# optical.net
KiCad netlist of a schematic drawn in Altium Designer
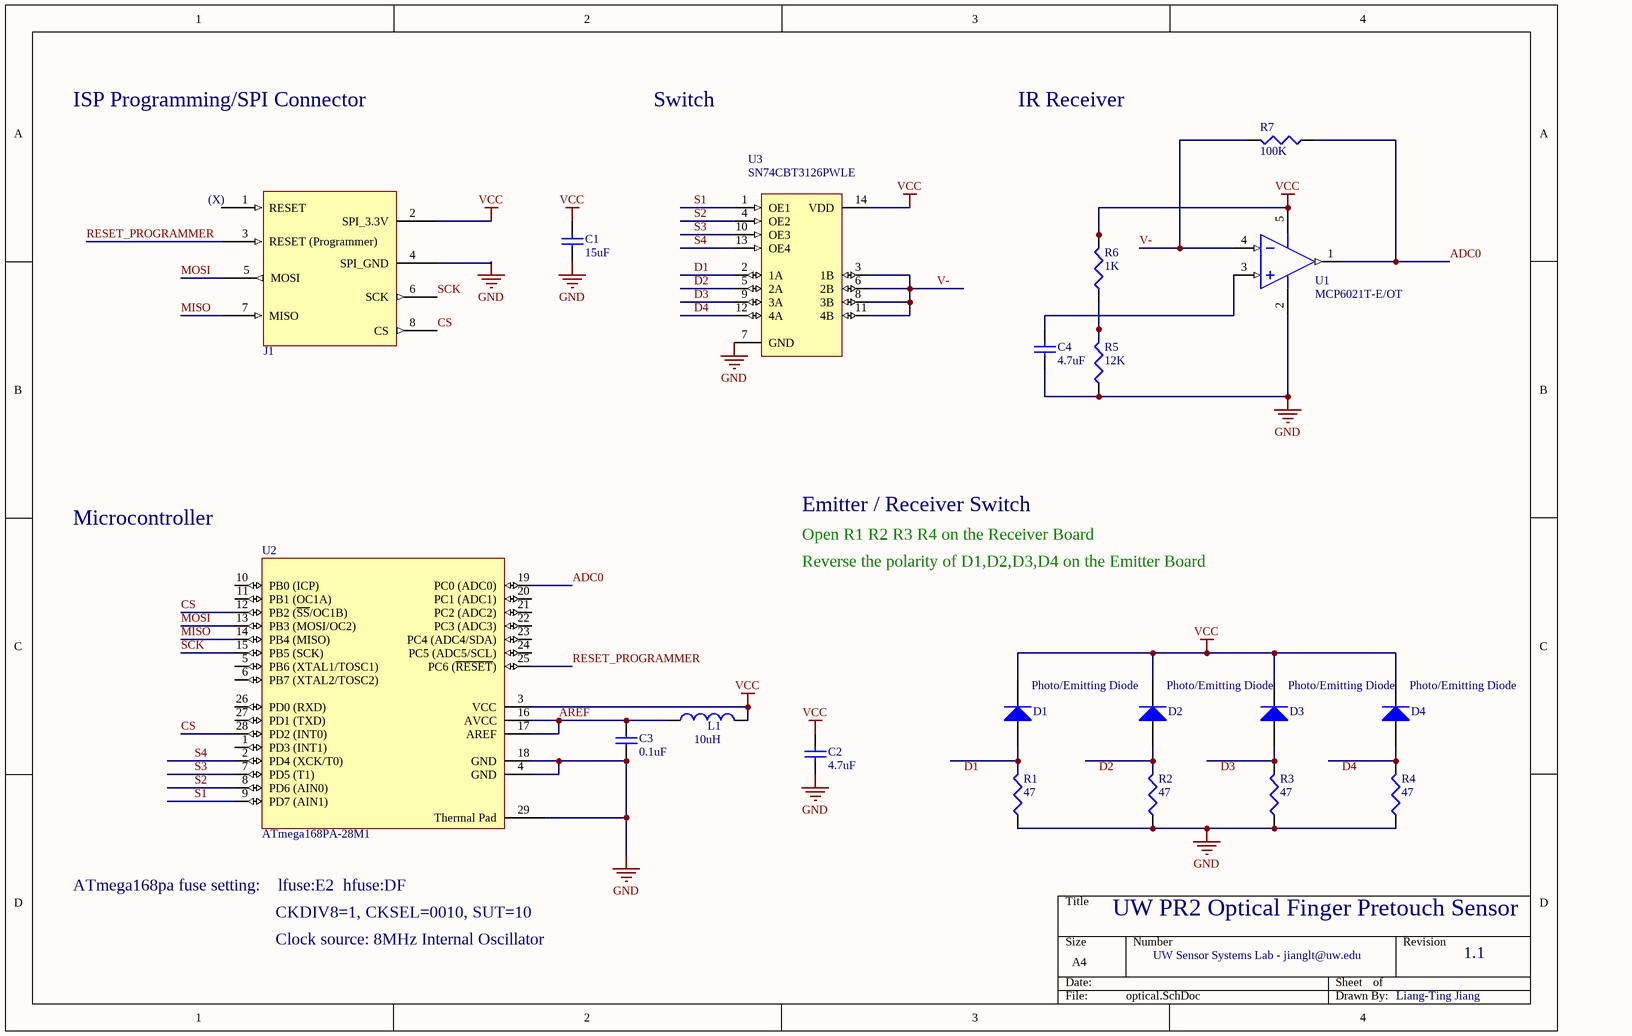
[diagram p0: optical.SchDoc]

(export (version "E")
  (design (tool "Eeschema 10.0.6"))
  (components
    (comp (ref "C1")
      (value "15uF")
      (footprint "CAPC1608N")
      (description "0603 SMD Capacitor")
      (fields (field (name "PUBLISHER") "Altium Limited"))
      (libsource (lib "Miscellaneous Devices") (part "Cap Semi"))
    )
    (comp (ref "C2")
      (value "4.7uF")
      (footprint "CAPC1608N")
      (description "0603 SMD Capacitor")
      (fields (field (name "PUBLISHER") "Altium Limited"))
      (libsource (lib "Miscellaneous Devices") (part "Cap Semi"))
    )
    (comp (ref "C3")
      (value "0.1uF")
      (footprint "CAPC1608N")
      (description "0603 SMD Capacitor")
      (fields (field (name "PUBLISHER") "Altium Limited"))
      (libsource (lib "Miscellaneous Devices") (part "Cap Semi"))
    )
    (comp (ref "C4")
      (value "4.7uF")
      (footprint "CAPC1608N")
      (description "0603 SMD Capacitor")
      (fields (field (name "PUBLISHER") "Altium Limited"))
      (libsource (lib "Miscellaneous Devices") (part "Cap Semi"))
    )
    (comp (ref "D1")
      (value "Photo/Emitting Diode")
      (footprint "Vishay VEMD/VSMB footprint")
      (description "Emitting/Photo Diode 940nm Gullwing")
      (fields (field (name "PUBLISHER") "Altium Limited"))
      (libsource (lib "Miscellaneous Devices") (part "Diode"))
    )
    (comp (ref "D2")
      (value "Photo/Emitting Diode")
      (footprint "Vishay VEMD/VSMB footprint")
      (description "Emitting/Photo Diode 940nm Gullwing")
      (fields (field (name "PUBLISHER") "Altium Limited"))
      (libsource (lib "Miscellaneous Devices") (part "Diode"))
    )
    (comp (ref "D3")
      (value "Photo/Emitting Diode")
      (footprint "Vishay VEMD/VSMB footprint")
      (description "Emitting/Photo Diode 940nm Gullwing")
      (fields (field (name "PUBLISHER") "Altium Limited"))
      (libsource (lib "Miscellaneous Devices") (part "Diode"))
    )
    (comp (ref "D4")
      (value "Photo/Emitting Diode")
      (footprint "Vishay VEMD/VSMB footprint")
      (description "Emitting/Photo Diode 940nm Gullwing")
      (fields (field (name "PUBLISHER") "Altium Limited"))
      (libsource (lib "Miscellaneous Devices") (part "Diode"))
    )
    (comp (ref "J1")
      (value "FFC 8-PIN Connector (1mm)")
      (footprint "Hirose FFC connector 8-Pin")
      (description "FFC 8-PIN Connector (1mm) (SMT)")
      (libsource (lib "UW_PR2_FINERTIP_COMPONENTS") (part "FFC Connector-8Pin-SMT-1mm"))
    )
    (comp (ref "L1")
      (value "10uH")
      (footprint "INDC1608N")
      (description "0603 SMD Inductor")
      (fields (field (name "PUBLISHER") "Altium Limited"))
      (libsource (lib "Miscellaneous Devices") (part "Inductor"))
    )
    (comp (ref "R1")
      (value "47")
      (footprint "RESC1608N")
      (description "0603 SMD Resistor")
      (fields (field (name "PUBLISHER") "Altium Limited"))
      (libsource (lib "Miscellaneous Devices") (part "Res3"))
    )
    (comp (ref "R2")
      (value "47")
      (footprint "RESC1608N")
      (description "0603 SMD Resistor")
      (fields (field (name "PUBLISHER") "Altium Limited"))
      (libsource (lib "Miscellaneous Devices") (part "Res3"))
    )
    (comp (ref "R3")
      (value "47")
      (footprint "RESC1608N")
      (description "0603 SMD Resistor")
      (fields (field (name "PUBLISHER") "Altium Limited"))
      (libsource (lib "Miscellaneous Devices") (part "Res3"))
    )
    (comp (ref "R4")
      (value "47")
      (footprint "RESC1608N")
      (description "0603 SMD Resistor")
      (fields (field (name "PUBLISHER") "Altium Limited"))
      (libsource (lib "Miscellaneous Devices") (part "Res3"))
    )
    (comp (ref "R5")
      (value "12K")
      (footprint "RESC1608N")
      (description "0603 SMD Resistor")
      (fields (field (name "PUBLISHER") "Altium Limited"))
      (libsource (lib "Miscellaneous Devices") (part "Res3"))
    )
    (comp (ref "R6")
      (value "1K")
      (footprint "RESC1608N")
      (description "0603 SMD Resistor")
      (fields (field (name "PUBLISHER") "Altium Limited"))
      (libsource (lib "Miscellaneous Devices") (part "Res3"))
    )
    (comp (ref "R7")
      (value "100K")
      (footprint "RESC1608N")
      (description "0603 SMD Resistor")
      (fields (field (name "PUBLISHER") "Altium Limited"))
      (libsource (lib "Miscellaneous Devices") (part "Res3"))
    )
    (comp (ref "U1")
      (value "MCP6021T-E/OT")
      (footprint "SOT-23-OT5_N")
      (fields (field (name "PUBLISHER") "Altium Limited"))
      (libsource (lib "Microchip Linear Devices") (part "MCP6021T-E/OT"))
    )
    (comp (ref "U2")
      (value "ATmega168PA-28M1")
      (footprint "28M1")
      (description "8-Bit AVR Microcontroller with 8K Bytes of In-System Programmable Flash Memory")
      (fields (field (name "PUBLISHER") "Altium Limited"))
      (libsource (lib "UW_PR2_FINERTIP_COMPONENTS") (part "ATmega168-28M1"))
    )
    (comp (ref "U3")
      (value "SN74CBT3126PWLE")
      (footprint "PW014_N")
      (description "Quadruple FET Bus Switch")
      (fields (field (name "PUBLISHER") "Altium Limited"))
      (libsource (lib "TI Logic Switch") (part "SN74CBT3126PWLE"))
    )
  )
  (nets
    (net (code "1") (name "/ADC0") (class "Default")
      (node (ref "R7") (pin "1") (pinfunction "1_1") (pintype "passive"))
      (node (ref "U1") (pin "1") (pinfunction "VOUT_1") (pintype "output"))
      (node (ref "U2") (pin "19") (pinfunction "PC0_(ADC0)_19") (pintype "bidirectional"))
    )
    (net (code "2") (name "/AREF") (class "Default")
      (node (ref "C3") (pin "2") (pinfunction "2_2") (pintype "passive"))
      (node (ref "L1") (pin "1") (pinfunction "1_1") (pintype "passive"))
      (node (ref "U2") (pin "16") (pinfunction "AVCC_16") (pintype "power_in"))
      (node (ref "U2") (pin "17") (pinfunction "AREF_17") (pintype "passive"))
    )
    (net (code "3") (name "/CS") (class "Default")
      (node (ref "J1") (pin "8") (pinfunction "CS_8") (pintype "output"))
      (node (ref "U2") (pin "12") (pinfunction "PB2_(~{SS}/OC1B)_12") (pintype "bidirectional"))
      (node (ref "U2") (pin "28") (pinfunction "PD2_(INT0)_28") (pintype "bidirectional"))
    )
    (net (code "4") (name "/D1") (class "Default")
      (node (ref "U3") (pin "2") (pinfunction "1A_2") (pintype "bidirectional"))
    )
    (net (code "5") (name "/D2") (class "Default")
      (node (ref "U3") (pin "5") (pinfunction "2A_5") (pintype "bidirectional"))
    )
    (net (code "6") (name "/D3") (class "Default")
      (node (ref "U3") (pin "9") (pinfunction "3A_9") (pintype "bidirectional"))
    )
    (net (code "7") (name "/D4") (class "Default")
      (node (ref "U3") (pin "12") (pinfunction "4A_12") (pintype "bidirectional"))
    )
    (net (code "8") (name "/MISO") (class "Default")
      (node (ref "J1") (pin "7") (pinfunction "MISO_7") (pintype "input"))
      (node (ref "U2") (pin "14") (pinfunction "PB4_(MISO)_14") (pintype "bidirectional"))
    )
    (net (code "9") (name "/MOSI") (class "Default")
      (node (ref "J1") (pin "5") (pinfunction "MOSI_5") (pintype "output"))
      (node (ref "U2") (pin "13") (pinfunction "PB3_(MOSI/OC2)_13") (pintype "bidirectional"))
    )
    (net (code "10") (name "/RESET_PROGRAMMER") (class "Default")
      (node (ref "J1") (pin "3") (pinfunction "RESET_(Programmer)_3") (pintype "input"))
      (node (ref "U2") (pin "25") (pinfunction "PC6_(~{RESET})_25") (pintype "bidirectional"))
    )
    (net (code "11") (name "/S1") (class "Default")
      (node (ref "U2") (pin "9") (pinfunction "PD7_(AIN1)_9") (pintype "bidirectional"))
      (node (ref "U3") (pin "1") (pinfunction "OE1_1") (pintype "input"))
    )
    (net (code "12") (name "/S2") (class "Default")
      (node (ref "U2") (pin "8") (pinfunction "PD6_(AIN0)_8") (pintype "bidirectional"))
      (node (ref "U3") (pin "4") (pinfunction "OE2_4") (pintype "input"))
    )
    (net (code "13") (name "/S3") (class "Default")
      (node (ref "U2") (pin "7") (pinfunction "PD5_(T1)_7") (pintype "bidirectional"))
      (node (ref "U3") (pin "10") (pinfunction "OE3_10") (pintype "input"))
    )
    (net (code "14") (name "/S4") (class "Default")
      (node (ref "U2") (pin "2") (pinfunction "PD4_(XCK/T0)_2") (pintype "bidirectional"))
      (node (ref "U3") (pin "13") (pinfunction "OE4_13") (pintype "input"))
    )
    (net (code "15") (name "/SCK") (class "Default")
      (node (ref "J1") (pin "6") (pinfunction "SCK_6") (pintype "output"))
      (node (ref "U2") (pin "15") (pinfunction "PB5_(SCK)_15") (pintype "bidirectional"))
    )
    (net (code "16") (name "/V-") (class "Default")
      (node (ref "R7") (pin "2") (pinfunction "2_2") (pintype "passive"))
      (node (ref "U1") (pin "4") (pinfunction "VIN-_4") (pintype "input"))
      (node (ref "U3") (pin "11") (pinfunction "4B_11") (pintype "bidirectional"))
      (node (ref "U3") (pin "3") (pinfunction "1B_3") (pintype "bidirectional"))
      (node (ref "U3") (pin "6") (pinfunction "2B_6") (pintype "bidirectional"))
      (node (ref "U3") (pin "8") (pinfunction "3B_8") (pintype "bidirectional"))
    )
    (net (code "17") (name "GND") (class "Default")
      (node (ref "C1") (pin "2") (pinfunction "2_2") (pintype "passive"))
      (node (ref "C2") (pin "2") (pinfunction "2_2") (pintype "passive"))
      (node (ref "C3") (pin "1") (pinfunction "1_1") (pintype "passive"))
      (node (ref "C4") (pin "2") (pinfunction "2_2") (pintype "passive"))
      (node (ref "J1") (pin "4") (pinfunction "SPI_GND_4") (pintype "power_in"))
      (node (ref "R1") (pin "1") (pinfunction "1_1") (pintype "passive"))
      (node (ref "R2") (pin "1") (pinfunction "1_1") (pintype "passive"))
      (node (ref "R3") (pin "1") (pinfunction "1_1") (pintype "passive"))
      (node (ref "R4") (pin "1") (pinfunction "1_1") (pintype "passive"))
      (node (ref "R5") (pin "1") (pinfunction "1_1") (pintype "passive"))
      (node (ref "U1") (pin "2") (pinfunction "VSS_2") (pintype "power_in"))
      (node (ref "U2") (pin "18") (pinfunction "GND_18") (pintype "power_in"))
      (node (ref "U2") (pin "29") (pinfunction "Thermal_Pad_29") (pintype "power_in"))
      (node (ref "U2") (pin "4") (pinfunction "GND_4") (pintype "power_in"))
      (node (ref "U3") (pin "7") (pinfunction "GND_7") (pintype "power_in"))
    )
    (net (code "18") (name "Net-(D1-A)") (class "Default")
      (node (ref "D1") (pin "1") (pinfunction "A_1") (pintype "passive"))
      (node (ref "R1") (pin "2") (pinfunction "2_2") (pintype "passive"))
    )
    (net (code "19") (name "Net-(D2-A)") (class "Default")
      (node (ref "D2") (pin "1") (pinfunction "A_1") (pintype "passive"))
      (node (ref "R2") (pin "2") (pinfunction "2_2") (pintype "passive"))
    )
    (net (code "20") (name "Net-(D3-A)") (class "Default")
      (node (ref "D3") (pin "1") (pinfunction "A_1") (pintype "passive"))
      (node (ref "R3") (pin "2") (pinfunction "2_2") (pintype "passive"))
    )
    (net (code "21") (name "Net-(D4-A)") (class "Default")
      (node (ref "D4") (pin "1") (pinfunction "A_1") (pintype "passive"))
      (node (ref "R4") (pin "2") (pinfunction "2_2") (pintype "passive"))
    )
    (net (code "22") (name "Net-(R5-Pad2)") (class "Default")
      (node (ref "R5") (pin "2") (pinfunction "2_2") (pintype "passive"))
      (node (ref "R6") (pin "1") (pinfunction "1_1") (pintype "passive"))
    )
    (net (code "23") (name "Net-(U1-VIN+)") (class "Default")
      (node (ref "C4") (pin "1") (pinfunction "1_1") (pintype "passive"))
      (node (ref "U1") (pin "3") (pinfunction "VIN+_3") (pintype "input"))
    )
    (net (code "24") (name "VCC") (class "Default")
      (node (ref "C1") (pin "1") (pinfunction "1_1") (pintype "passive"))
      (node (ref "C2") (pin "1") (pinfunction "1_1") (pintype "passive"))
      (node (ref "D1") (pin "2") (pinfunction "K_2") (pintype "passive"))
      (node (ref "D2") (pin "2") (pinfunction "K_2") (pintype "passive"))
      (node (ref "D3") (pin "2") (pinfunction "K_2") (pintype "passive"))
      (node (ref "D4") (pin "2") (pinfunction "K_2") (pintype "passive"))
      (node (ref "J1") (pin "2") (pinfunction "SPI_3.3V_2") (pintype "power_in"))
      (node (ref "L1") (pin "2") (pinfunction "2_2") (pintype "passive"))
      (node (ref "R6") (pin "2") (pinfunction "2_2") (pintype "passive"))
      (node (ref "U1") (pin "5") (pinfunction "VDD_5") (pintype "power_in"))
      (node (ref "U2") (pin "3") (pinfunction "VCC_3") (pintype "power_in"))
      (node (ref "U3") (pin "14") (pinfunction "VDD_14") (pintype "power_in"))
    )
    (net (code "25") (name "unconnected-(J1-RESET-Pad1)") (class "Default")
      (node (ref "J1") (pin "1") (pinfunction "RESET_1") (pintype "input"))
    )
    (net (code "26") (name "unconnected-(U2-PB0_(ICP)-Pad10)") (class "Default")
      (node (ref "U2") (pin "10") (pinfunction "PB0_(ICP)_10") (pintype "bidirectional"))
    )
    (net (code "27") (name "unconnected-(U2-PB1_(OC1A)-Pad11)") (class "Default")
      (node (ref "U2") (pin "11") (pinfunction "PB1_(OC1A)_11") (pintype "bidirectional"))
    )
    (net (code "28") (name "unconnected-(U2-PB6_(XTAL1{slash}TOSC1)-Pad5)") (class "Default")
      (node (ref "U2") (pin "5") (pinfunction "PB6_(XTAL1/TOSC1)_5") (pintype "bidirectional"))
    )
    (net (code "29") (name "unconnected-(U2-PB7_(XTAL2{slash}TOSC2)-Pad6)") (class "Default")
      (node (ref "U2") (pin "6") (pinfunction "PB7_(XTAL2/TOSC2)_6") (pintype "bidirectional"))
    )
    (net (code "30") (name "unconnected-(U2-PC1_(ADC1)-Pad20)") (class "Default")
      (node (ref "U2") (pin "20") (pinfunction "PC1_(ADC1)_20") (pintype "bidirectional"))
    )
    (net (code "31") (name "unconnected-(U2-PC2_(ADC2)-Pad21)") (class "Default")
      (node (ref "U2") (pin "21") (pinfunction "PC2_(ADC2)_21") (pintype "bidirectional"))
    )
    (net (code "32") (name "unconnected-(U2-PC3_(ADC3)-Pad22)") (class "Default")
      (node (ref "U2") (pin "22") (pinfunction "PC3_(ADC3)_22") (pintype "bidirectional"))
    )
    (net (code "33") (name "unconnected-(U2-PC4_(ADC4{slash}SDA)-Pad23)") (class "Default")
      (node (ref "U2") (pin "23") (pinfunction "PC4_(ADC4/SDA)_23") (pintype "bidirectional"))
    )
    (net (code "34") (name "unconnected-(U2-PC5_(ADC5{slash}SCL)-Pad24)") (class "Default")
      (node (ref "U2") (pin "24") (pinfunction "PC5_(ADC5/SCL)_24") (pintype "bidirectional"))
    )
    (net (code "35") (name "unconnected-(U2-PD0_(RXD)-Pad26)") (class "Default")
      (node (ref "U2") (pin "26") (pinfunction "PD0_(RXD)_26") (pintype "bidirectional"))
    )
    (net (code "36") (name "unconnected-(U2-PD1_(TXD)-Pad27)") (class "Default")
      (node (ref "U2") (pin "27") (pinfunction "PD1_(TXD)_27") (pintype "bidirectional"))
    )
    (net (code "37") (name "unconnected-(U2-PD3_(INT1)-Pad1)") (class "Default")
      (node (ref "U2") (pin "1") (pinfunction "PD3_(INT1)_1") (pintype "bidirectional"))
    )
  )
)
